# design.net
KiCad netlist of a schematic drawn in Altium Designer
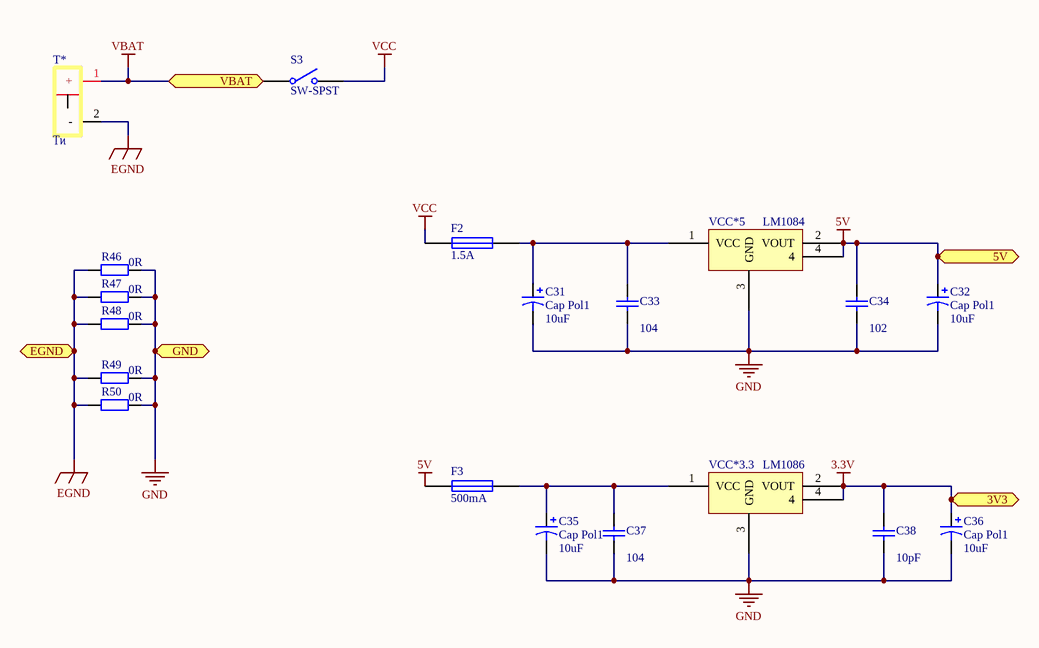
[diagram p0: 电源.SchDoc]

(export (version "E")
  (design (tool "Eeschema 10.0.6"))
  (components
    (comp (ref "C31")
      (value "Cap Pol1")
      (footprint "1206(2)")
      (description "Polarized Capacitor (Radial)")
      (fields (field (name "ALTIUM_VALUE") "10uF") (field (name "PUBLISHER") "Altium Limited"))
      (libsource (lib "Miscellaneous Devices") (part "Cap Pol1"))
    )
    (comp (ref "C32")
      (value "Cap Pol1")
      (footprint "1206(2)")
      (description "Polarized Capacitor (Radial)")
      (fields (field (name "ALTIUM_VALUE") "10uF") (field (name "PUBLISHER") "Altium Limited"))
      (libsource (lib "Miscellaneous Devices") (part "Cap Pol1"))
    )
    (comp (ref "C33")
      (value "104")
      (footprint "C2012")
      (description "贴片电容")
      (fields (field (name "Comment") "Cap") (field (name "PUBLISHER") "Altium Limited"))
      (libsource (lib "Sparks") (part "Cap"))
    )
    (comp (ref "C34")
      (value "102")
      (footprint "C2012")
      (description "贴片电容")
      (fields (field (name "Comment") "Cap") (field (name "PUBLISHER") "Altium Limited"))
      (libsource (lib "Sparks") (part "Cap"))
    )
    (comp (ref "C35")
      (value "Cap Pol1")
      (footprint "1206(2)")
      (description "Polarized Capacitor (Radial)")
      (fields (field (name "ALTIUM_VALUE") "10uF") (field (name "PUBLISHER") "Altium Limited"))
      (libsource (lib "Miscellaneous Devices") (part "Cap Pol1"))
    )
    (comp (ref "C36")
      (value "Cap Pol1")
      (footprint "1206(2)")
      (description "Polarized Capacitor (Radial)")
      (fields (field (name "ALTIUM_VALUE") "10uF") (field (name "PUBLISHER") "Altium Limited"))
      (libsource (lib "Miscellaneous Devices") (part "Cap Pol1"))
    )
    (comp (ref "C37")
      (value "104")
      (footprint "C2012")
      (description "贴片电容")
      (fields (field (name "Comment") "Cap") (field (name "PUBLISHER") "Altium Limited"))
      (libsource (lib "Sparks") (part "Cap"))
    )
    (comp (ref "C38")
      (value "10pF")
      (footprint "C2012")
      (description "贴片电容")
      (fields (field (name "Comment") "Cap") (field (name "PUBLISHER") "Altium Limited"))
      (libsource (lib "Sparks") (part "Cap"))
    )
    (comp (ref "F2")
      (value "1.5A")
      (footprint "1206(2)")
      (description "Fuse")
      (fields (field (name "PUBLISHER") "Altium Limited"))
      (libsource (lib "K60-V4.0") (part "Fuse 1"))
    )
    (comp (ref "F3")
      (value "500mA")
      (footprint "1206(2)")
      (description "Fuse")
      (fields (field (name "PUBLISHER") "Altium Limited"))
      (libsource (lib "K60-V4.0") (part "Fuse 1"))
    )
    (comp (ref "R46")
      (value "0R")
      (footprint "1206(2)")
      (description "Resistor")
      (fields (field (name "Comment") "Res2") (field (name "PUBLISHER") "Altium Limited"))
      (libsource (lib "Miscellaneous Devices") (part "Res2"))
    )
    (comp (ref "R47")
      (value "0R")
      (footprint "1206(2)")
      (description "Resistor")
      (fields (field (name "Comment") "Res2") (field (name "PUBLISHER") "Altium Limited"))
      (libsource (lib "Miscellaneous Devices") (part "Res2"))
    )
    (comp (ref "R48")
      (value "0R")
      (footprint "1206(2)")
      (description "Resistor")
      (fields (field (name "Comment") "Res2") (field (name "PUBLISHER") "Altium Limited"))
      (libsource (lib "Miscellaneous Devices") (part "Res2"))
    )
    (comp (ref "R49")
      (value "0R")
      (footprint "1206(2)")
      (description "Resistor")
      (fields (field (name "Comment") "Res2") (field (name "PUBLISHER") "Altium Limited"))
      (libsource (lib "Miscellaneous Devices") (part "Res2"))
    )
    (comp (ref "R50")
      (value "0R")
      (footprint "1206(2)")
      (description "Resistor")
      (fields (field (name "Comment") "Res2") (field (name "PUBLISHER") "Altium Limited"))
      (libsource (lib "Miscellaneous Devices") (part "Res2"))
    )
    (comp (ref "S3")
      (value "SW-SPST")
      (footprint "SW-125V6A(-)")
      (description "Single-Pole, Single-Throw Switch")
      (fields (field (name "PUBLISHER") "Altium Limited"))
      (libsource (lib "Miscellaneous Devices") (part "SW-SPST"))
    )
    (comp (ref "T*") (value "T头") (footprint "T插") (libsource (lib "原理图") (part "T头")))
    (comp (ref "VCC*3.3") (value "LM1086") (footprint "DPAK LM2940") (libsource (lib "2号库") (part "LM1086")))
    (comp (ref "VCC*5") (value "LM1084") (footprint "DPAK LM2940") (libsource (lib "2号库") (part "LM1086")))
  )
  (nets
    (net (code "1") (name "3.3V") (class "Default")
      (node (ref "C36") (pin "1") (pinfunction "1_1") (pintype "passive"))
      (node (ref "C38") (pin "2") (pinfunction "2_2") (pintype "passive"))
      (node (ref "VCC*3.3") (pin "2") (pinfunction "VOUT_2") (pintype "passive"))
      (node (ref "VCC*3.3") (pin "4") (pinfunction "4_4") (pintype "passive"))
    )
    (net (code "2") (name "5V") (class "Default")
      (node (ref "C32") (pin "1") (pinfunction "1_1") (pintype "passive"))
      (node (ref "C34") (pin "2") (pinfunction "2_2") (pintype "passive"))
      (node (ref "F3") (pin "1") (pinfunction "1_1") (pintype "passive"))
      (node (ref "VCC*5") (pin "2") (pinfunction "VOUT_2") (pintype "passive"))
      (node (ref "VCC*5") (pin "4") (pinfunction "4_4") (pintype "passive"))
    )
    (net (code "3") (name "EGND") (class "Default")
      (node (ref "R46") (pin "2") (pinfunction "2_2") (pintype "passive"))
      (node (ref "R47") (pin "2") (pinfunction "2_2") (pintype "passive"))
      (node (ref "R48") (pin "2") (pinfunction "2_2") (pintype "passive"))
      (node (ref "R49") (pin "2") (pinfunction "2_2") (pintype "passive"))
      (node (ref "R50") (pin "2") (pinfunction "2_2") (pintype "passive"))
      (node (ref "T*") (pin "2") (pinfunction "-_2") (pintype "passive"))
    )
    (net (code "4") (name "GND") (class "Default")
      (node (ref "C31") (pin "2") (pinfunction "2_2") (pintype "passive"))
      (node (ref "C32") (pin "2") (pinfunction "2_2") (pintype "passive"))
      (node (ref "C33") (pin "1") (pinfunction "1_1") (pintype "passive"))
      (node (ref "C34") (pin "1") (pinfunction "1_1") (pintype "passive"))
      (node (ref "C35") (pin "2") (pinfunction "2_2") (pintype "passive"))
      (node (ref "C36") (pin "2") (pinfunction "2_2") (pintype "passive"))
      (node (ref "C37") (pin "1") (pinfunction "1_1") (pintype "passive"))
      (node (ref "C38") (pin "1") (pinfunction "1_1") (pintype "passive"))
      (node (ref "R46") (pin "1") (pinfunction "1_1") (pintype "passive"))
      (node (ref "R47") (pin "1") (pinfunction "1_1") (pintype "passive"))
      (node (ref "R48") (pin "1") (pinfunction "1_1") (pintype "passive"))
      (node (ref "R49") (pin "1") (pinfunction "1_1") (pintype "passive"))
      (node (ref "R50") (pin "1") (pinfunction "1_1") (pintype "passive"))
      (node (ref "VCC*3.3") (pin "3") (pinfunction "GND_3") (pintype "passive"))
      (node (ref "VCC*5") (pin "3") (pinfunction "GND_3") (pintype "passive"))
    )
    (net (code "5") (name "Net-(VCC*3.3-VCC)") (class "Default")
      (node (ref "C35") (pin "1") (pinfunction "1_1") (pintype "passive"))
      (node (ref "C37") (pin "2") (pinfunction "2_2") (pintype "passive"))
      (node (ref "F3") (pin "2") (pinfunction "2_2") (pintype "passive"))
      (node (ref "VCC*3.3") (pin "1") (pinfunction "VCC_1") (pintype "passive"))
    )
    (net (code "6") (name "Net-(VCC*5-VCC)") (class "Default")
      (node (ref "C31") (pin "1") (pinfunction "1_1") (pintype "passive"))
      (node (ref "C33") (pin "2") (pinfunction "2_2") (pintype "passive"))
      (node (ref "F2") (pin "2") (pinfunction "2_2") (pintype "passive"))
      (node (ref "VCC*5") (pin "1") (pinfunction "VCC_1") (pintype "passive"))
    )
    (net (code "7") (name "VBAT") (class "Default")
      (node (ref "S3") (pin "1") (pinfunction "COMMON_1") (pintype "passive"))
      (node (ref "T*") (pin "1") (pinfunction "+_1") (pintype "power_in"))
    )
    (net (code "8") (name "VCC") (class "Default")
      (node (ref "F2") (pin "1") (pinfunction "1_1") (pintype "passive"))
      (node (ref "S3") (pin "2") (pinfunction "NO_2") (pintype "passive"))
    )
  )
)
